# 1_power.net
KiCad netlist of a schematic drawn in Altium Designer
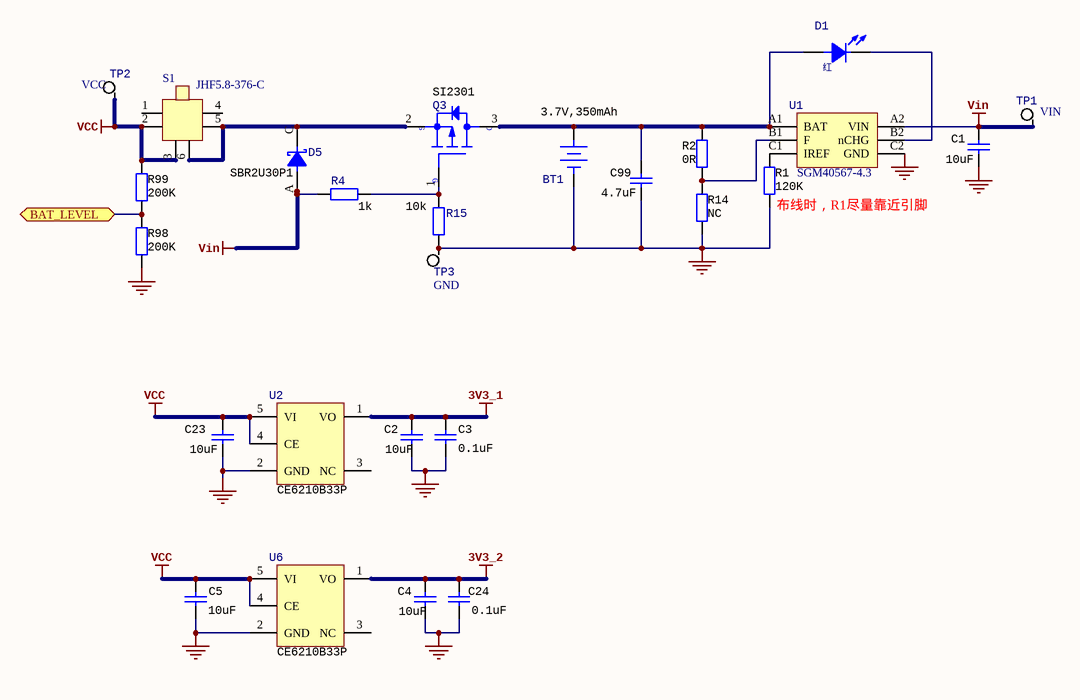
[diagram p0: 1.power.SchDoc]

(export (version "E")
  (design (tool "Eeschema 10.0.6"))
  (components
    (comp (ref "BT1")
      (value "3.7V,350mAh")
      (footprint "2P/1.0MM立式贴片座子")
      (description "4.2V Li-lon")
      (fields (field (name "MANUFACTURER") "?"))
      (libsource (lib "03.常用器件") (part "Battery"))
    )
    (comp (ref "C1")
      (value "10uF")
      (footprint "C0603")
      (description "CAP, CERM, 0.01uF, 100V, +/-5%, X7R, 0603")
      (fields (field (name "PARTNUMBER") "06031C103JAT2A") (field (name "MANUFACTURER") "AVX"))
      (libsource (lib "03.常用器件") (part "CAP1_npol"))
    )
    (comp (ref "C2")
      (value "10uF")
      (footprint "0603")
      (description "CAP, CERM, 0.01uF, 100V, +/-5%, X7R, 0603")
      (fields (field (name "PARTNUMBER") "06031C103JAT2A") (field (name "MANUFACTURER") "AVX"))
      (libsource (lib "03.常用器件") (part "CAP1_npol"))
    )
    (comp (ref "C3")
      (value "0.1uF")
      (footprint "0402")
      (description "CAP, CERM, 0.01uF, 100V, +/-5%, X7R, 0603")
      (fields (field (name "PARTNUMBER") "06031C103JAT2A") (field (name "MANUFACTURER") "AVX"))
      (libsource (lib "03.常用器件") (part "CAP1_npol"))
    )
    (comp (ref "C4")
      (value "10uF")
      (footprint "0603")
      (description "CAP, CERM, 0.01uF, 100V, +/-5%, X7R, 0603")
      (fields (field (name "PARTNUMBER") "06031C103JAT2A") (field (name "MANUFACTURER") "AVX"))
      (libsource (lib "03.常用器件") (part "CAP1_npol"))
    )
    (comp (ref "C5")
      (value "10uF")
      (footprint "0603")
      (description "CAP, CERM, 0.01uF, 100V, +/-5%, X7R, 0603")
      (fields (field (name "PARTNUMBER") "06031C103JAT2A") (field (name "MANUFACTURER") "AVX"))
      (libsource (lib "03.常用器件") (part "CAP1_npol"))
    )
    (comp (ref "C23")
      (value "10uF")
      (footprint "0603")
      (description "CAP, CERM, 0.01uF, 100V, +/-5%, X7R, 0603")
      (fields (field (name "PARTNUMBER") "06031C103JAT2A") (field (name "MANUFACTURER") "AVX"))
      (libsource (lib "03.常用器件") (part "CAP1_npol"))
    )
    (comp (ref "C24")
      (value "0.1uF")
      (footprint "0402")
      (description "CAP, CERM, 0.01uF, 100V, +/-5%, X7R, 0603")
      (fields (field (name "PARTNUMBER") "06031C103JAT2A") (field (name "MANUFACTURER") "AVX"))
      (libsource (lib "03.常用器件") (part "CAP1_npol"))
    )
    (comp (ref "C99")
      (value "4.7uF")
      (footprint "C0603")
      (description "CAP, CERM, 0.01uF, 100V, +/-5%, X7R, 0603")
      (fields (field (name "PARTNUMBER") "06031C103JAT2A") (field (name "MANUFACTURER") "AVX"))
      (libsource (lib "03.常用器件") (part "CAP1_npol"))
    )
    (comp (ref "D1")
      (value "红")
      (footprint "0603LED")
      (fields (field (name "MANUFACTURER") "?"))
      (libsource (lib "03.常用器件") (part "LED1"))
    )
    (comp (ref "D5")
      (value "SBR2U30P1")
      (footprint "POWERDI123")
      (fields (field (name "PARTNUMBER") "?") (field (name "PUBLISHER") "Altium Limited"))
      (libsource (lib "03.常用器件") (part "Diode_Schottky"))
    )
    (comp (ref "Q3")
      (value "SI2301")
      (footprint "SOT23-3")
      (fields (field (name "MANUFACTURER") "?"))
      (libsource (lib "03.常用器件") (part "PMOS"))
    )
    (comp (ref "R1")
      (value "120K")
      (footprint "R0402")
      (description "RES, 1.0k ohm, 5%, 0.1W, 0603")
      (fields
        (field (name "PARTNUMBER") "RC0603JR-071KL")
        (field (name "MANUFACTURER") "Yageo America")
        (field (name "PUBLISHER") "Texas Instruments")
      )
      (libsource (lib "03.常用器件") (part "RES1"))
    )
    (comp (ref "R2")
      (value "0R")
      (footprint "R0402")
      (description "RES, 1.0k ohm, 5%, 0.1W, 0603")
      (fields
        (field (name "PARTNUMBER") "RC0603JR-071KL")
        (field (name "MANUFACTURER") "Yageo America")
        (field (name "PUBLISHER") "Texas Instruments")
      )
      (libsource (lib "") (part "RES1_1"))
    )
    (comp (ref "R4")
      (value "1k")
      (footprint "R0402")
      (description "Resistor")
      (fields (field (name "PUBLISHER") "Altium Limited"))
      (libsource (lib "") (part "Res2_1"))
    )
    (comp (ref "R14")
      (value "NC")
      (footprint "R0402")
      (description "RES, 1.0k ohm, 5%, 0.1W, 0603")
      (fields
        (field (name "PARTNUMBER") "RC0603JR-071KL")
        (field (name "MANUFACTURER") "Yageo America")
        (field (name "PUBLISHER") "Texas Instruments")
      )
      (libsource (lib "") (part "RES1_1"))
    )
    (comp (ref "R15")
      (value "10k")
      (footprint "R0402")
      (description "Resistor")
      (fields (field (name "PUBLISHER") "Altium Limited"))
      (libsource (lib "Miscellaneous Devices") (part "Res2"))
    )
    (comp (ref "R98")
      (value "200K")
      (footprint "R0402")
      (description "RES, 1.0k ohm, 5%, 0.1W, 0603")
      (fields
        (field (name "PARTNUMBER") "RC0603JR-071KL")
        (field (name "MANUFACTURER") "Yageo America")
        (field (name "PUBLISHER") "Texas Instruments")
      )
      (libsource (lib "03.常用器件") (part "RES1"))
    )
    (comp (ref "R99")
      (value "200K")
      (footprint "R0402")
      (description "RES, 1.0k ohm, 5%, 0.1W, 0603")
      (fields
        (field (name "PARTNUMBER") "RC0603JR-071KL")
        (field (name "MANUFACTURER") "Yageo America")
        (field (name "PUBLISHER") "Texas Instruments")
      )
      (libsource (lib "03.常用器件") (part "RES1"))
    )
    (comp (ref "S1") (value "JHF5.8-376-C") (libsource (lib "Schlib1") (part "JHF5.8-376-C")))
    (comp (ref "TP1")
      (value "VIN")
      (footprint "测试点")
      (description "Test Point")
      (libsource (lib "my_Schlib") (part "TP"))
    )
    (comp (ref "TP2")
      (value "VCC")
      (footprint "测试点")
      (description "Test Point")
      (libsource (lib "my_Schlib") (part "TP"))
    )
    (comp (ref "TP3")
      (value "GND")
      (footprint "测试点")
      (description "Test Point")
      (libsource (lib "my_Schlib") (part "TP"))
    )
    (comp (ref "U1")
      (value "SGM40567-4.3")
      (footprint "SGM40567")
      (description "充电IC")
      (libsource (lib "SGM40567") (part "SGM40567"))
    )
    (comp (ref "U2")
      (value "CE6210B33P")
      (footprint "SOT89-5")
      (libsource (lib "altium-import") (part "root_0_AP2112K_"))
    )
    (comp (ref "U6")
      (value "CE6210B33P")
      (footprint "SOT89-5")
      (libsource (lib "altium-import") (part "root_0_AP2112K_"))
    )
  )
  (nets
    (net (code "1") (name "/BAT_LEVEL") (class "Default")
      (node (ref "R98") (pin "2") (pinfunction "2_2") (pintype "passive"))
      (node (ref "R99") (pin "1") (pinfunction "1_1") (pintype "passive"))
    )
    (net (code "2") (name "3V3_1") (class "Default")
      (node (ref "C2") (pin "1") (pinfunction "1_1") (pintype "passive"))
      (node (ref "C3") (pin "2") (pinfunction "2_2") (pintype "passive"))
      (node (ref "U2") (pin "1") (pinfunction "VO_1") (pintype "passive"))
    )
    (net (code "3") (name "3V3_2") (class "Default")
      (node (ref "C24") (pin "2") (pinfunction "2_2") (pintype "passive"))
      (node (ref "C4") (pin "1") (pinfunction "1_1") (pintype "passive"))
      (node (ref "U6") (pin "1") (pinfunction "VO_1") (pintype "passive"))
    )
    (net (code "4") (name "<NO NET>") (class "Default")
      (node (ref "BT1") (pin "2") (pinfunction "-_2") (pintype "passive"))
      (node (ref "C1") (pin "2") (pinfunction "2_2") (pintype "passive"))
      (node (ref "C2") (pin "2") (pinfunction "2_2") (pintype "passive"))
      (node (ref "C23") (pin "2") (pinfunction "2_2") (pintype "passive"))
      (node (ref "C24") (pin "1") (pinfunction "1_1") (pintype "passive"))
      (node (ref "C3") (pin "1") (pinfunction "1_1") (pintype "passive"))
      (node (ref "C4") (pin "2") (pinfunction "2_2") (pintype "passive"))
      (node (ref "C5") (pin "2") (pinfunction "2_2") (pintype "passive"))
      (node (ref "C99") (pin "2") (pinfunction "2_2") (pintype "passive"))
      (node (ref "R1") (pin "1") (pinfunction "1_1") (pintype "passive"))
      (node (ref "R14") (pin "2") (pinfunction "2_2") (pintype "passive"))
      (node (ref "R15") (pin "1") (pinfunction "1_1") (pintype "passive"))
      (node (ref "R98") (pin "1") (pinfunction "1_1") (pintype "passive"))
      (node (ref "TP3") (pin "1") (pinfunction "1_1") (pintype "passive"))
      (node (ref "U1") (pin "C2") (pinfunction "GND_C2") (pintype "passive"))
      (node (ref "U2") (pin "2") (pinfunction "GND_2") (pintype "passive"))
      (node (ref "U6") (pin "2") (pinfunction "GND_2") (pintype "passive"))
    )
    (net (code "5") (name "Net-(BT1-+)") (class "Default")
      (node (ref "BT1") (pin "1") (pinfunction "+_1") (pintype "passive"))
      (node (ref "C99") (pin "1") (pinfunction "1_1") (pintype "passive"))
      (node (ref "D1") (pin "A") (pinfunction "ANODE_A") (pintype "passive"))
      (node (ref "Q3") (pin "3") (pinfunction "DRAIN_3") (pintype "passive"))
      (node (ref "R2") (pin "1") (pinfunction "1_1") (pintype "passive"))
      (node (ref "U1") (pin "A1") (pinfunction "BAT_A1") (pintype "passive"))
    )
    (net (code "6") (name "Net-(D1-CATHODE)") (class "Default")
      (node (ref "D1") (pin "C") (pinfunction "CATHODE_C") (pintype "passive"))
      (node (ref "U1") (pin "B2") (pinfunction "nCHG_B2") (pintype "passive"))
    )
    (net (code "7") (name "Net-(D5-CATHODE)") (class "Default")
      (node (ref "D5") (pin "C") (pinfunction "CATHODE_C") (pintype "passive"))
      (node (ref "Q3") (pin "2") (pinfunction "SOURCE_2") (pintype "passive"))
      (node (ref "S1") (pin "5") (pinfunction "5_5") (pintype "passive"))
      (node (ref "S1") (pin "6") (pinfunction "6_6") (pintype "passive"))
    )
    (net (code "8") (name "Net-(Q3-GATE)") (class "Default")
      (node (ref "Q3") (pin "1") (pinfunction "GATE_1") (pintype "passive"))
      (node (ref "R15") (pin "2") (pinfunction "2_2") (pintype "passive"))
      (node (ref "R4") (pin "1") (pinfunction "1_1") (pintype "passive"))
    )
    (net (code "9") (name "Net-(U1-F)") (class "Default")
      (node (ref "R14") (pin "1") (pinfunction "1_1") (pintype "passive"))
      (node (ref "R2") (pin "2") (pinfunction "2_2") (pintype "passive"))
      (node (ref "U1") (pin "B1") (pinfunction "F_B1") (pintype "passive"))
    )
    (net (code "10") (name "Net-(U1-IREF)") (class "Default")
      (node (ref "R1") (pin "2") (pinfunction "2_2") (pintype "passive"))
      (node (ref "U1") (pin "C1") (pinfunction "IREF_C1") (pintype "passive"))
    )
    (net (code "11") (name "VCC") (class "Default")
      (node (ref "C23") (pin "1") (pinfunction "1_1") (pintype "passive"))
      (node (ref "C5") (pin "1") (pinfunction "1_1") (pintype "passive"))
      (node (ref "R99") (pin "2") (pinfunction "2_2") (pintype "passive"))
      (node (ref "S1") (pin "2") (pinfunction "2_2") (pintype "passive"))
      (node (ref "S1") (pin "3") (pinfunction "3_3") (pintype "passive"))
      (node (ref "TP2") (pin "1") (pinfunction "1_1") (pintype "passive"))
      (node (ref "U2") (pin "4") (pinfunction "CE_4") (pintype "passive"))
      (node (ref "U2") (pin "5") (pinfunction "VI_5") (pintype "passive"))
      (node (ref "U6") (pin "4") (pinfunction "CE_4") (pintype "passive"))
      (node (ref "U6") (pin "5") (pinfunction "VI_5") (pintype "passive"))
    )
    (net (code "12") (name "Vin") (class "Default")
      (node (ref "C1") (pin "1") (pinfunction "1_1") (pintype "passive"))
      (node (ref "D5") (pin "A") (pinfunction "ANODE_A") (pintype "passive"))
      (node (ref "R4") (pin "2") (pinfunction "2_2") (pintype "passive"))
      (node (ref "TP1") (pin "1") (pinfunction "1_1") (pintype "passive"))
      (node (ref "U1") (pin "A2") (pinfunction "VIN_A2") (pintype "passive"))
    )
    (net (code "13") (name "unconnected-(S1-Pad1)") (class "Default")
      (node (ref "S1") (pin "1") (pinfunction "1_1") (pintype "passive"))
    )
    (net (code "14") (name "unconnected-(S1-Pad4)") (class "Default")
      (node (ref "S1") (pin "4") (pinfunction "4_4") (pintype "passive"))
    )
    (net (code "15") (name "unconnected-(U2-NC-Pad3)") (class "Default")
      (node (ref "U2") (pin "3") (pinfunction "NC_3") (pintype "passive"))
    )
    (net (code "16") (name "unconnected-(U6-NC-Pad3)") (class "Default")
      (node (ref "U6") (pin "3") (pinfunction "NC_3") (pintype "passive"))
    )
  )
)
